# Sheet2.net
KiCad netlist of a schematic drawn in Altium Designer
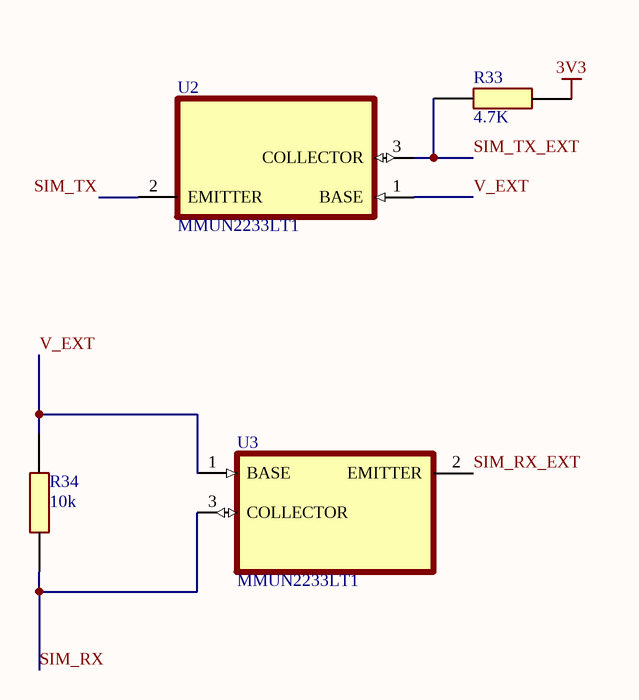
[diagram p0: Sheet2.SchDoc]

(export (version "E")
  (design (tool "Eeschema 10.0.6"))
  (components
    (comp (ref "R33")
      (value "4.7K")
      (footprint "BGA129C50P13X13_700X700X60:RESC1608X55N")
      (description "Resistor")
      (fields
        (field (name "MANUFACTURER_PART_NUMBER") "RC0603FR-074K7L")
        (field (name "MOUSER PART NUMBER") "603-RC0603FR-074K7L")
      )
      (libsource (lib "STM32WB55VGQ6") (part "RC0603FR-074K7L"))
    )
    (comp (ref "R34")
      (value "10k")
      (footprint "BGA129C50P13X13_700X700X60:RESC2012X60N")
      (description "Resistor")
      (fields
        (field (name "MANUFACTURER_PART_NUMBER") "CR0805-FX-1002ELF")
        (field (name "MOUSER PART NUMBER") "652-CR0805FX-1002ELF")
      )
      (libsource (lib "STM32WB55VGQ6") (part "CR0805-FX-1002ELF"))
    )
    (comp (ref "U2")
      (value "MMUN2233LT1")
      (footprint "SOT95P237X111-3N")
      (fields (field (name "MF") "ON Semiconductor"))
      (libsource (lib "") (part "MMUN2233LT1_1"))
    )
    (comp (ref "U3")
      (value "MMUN2233LT1")
      (footprint "SOT95P237X111-3N")
      (fields (field (name "MF") "ON Semiconductor"))
      (libsource (lib "MMUN2233LT1 (1)") (part "MMUN2233LT1"))
    )
  )
  (nets
    (net (code "1") (name "/SIM_RX") (class "Default")
      (node (ref "R34") (pin "1") (pinfunction "1_1") (pintype "passive"))
      (node (ref "U3") (pin "3") (pinfunction "COLLECTOR_3") (pintype "bidirectional"))
    )
    (net (code "2") (name "/SIM_RX_EXT") (class "Default")
      (node (ref "U3") (pin "2") (pinfunction "EMITTER_2") (pintype "power_in"))
    )
    (net (code "3") (name "/SIM_TX") (class "Default")
      (node (ref "U2") (pin "2") (pinfunction "EMITTER_2") (pintype "power_in"))
    )
    (net (code "4") (name "/SIM_TX_EXT") (class "Default")
      (node (ref "R33") (pin "1") (pinfunction "1_1") (pintype "passive"))
      (node (ref "U2") (pin "3") (pinfunction "COLLECTOR_3") (pintype "bidirectional"))
    )
    (net (code "5") (name "/V_EXT") (class "Default")
      (node (ref "R34") (pin "2") (pinfunction "2_2") (pintype "passive"))
      (node (ref "U2") (pin "1") (pinfunction "BASE_1") (pintype "input"))
      (node (ref "U3") (pin "1") (pinfunction "BASE_1") (pintype "input"))
    )
    (net (code "6") (name "3V3") (class "Default")
      (node (ref "R33") (pin "2") (pinfunction "2_2") (pintype "passive"))
    )
  )
)
